# poe.net
KiCad netlist of a schematic drawn in EAGLE
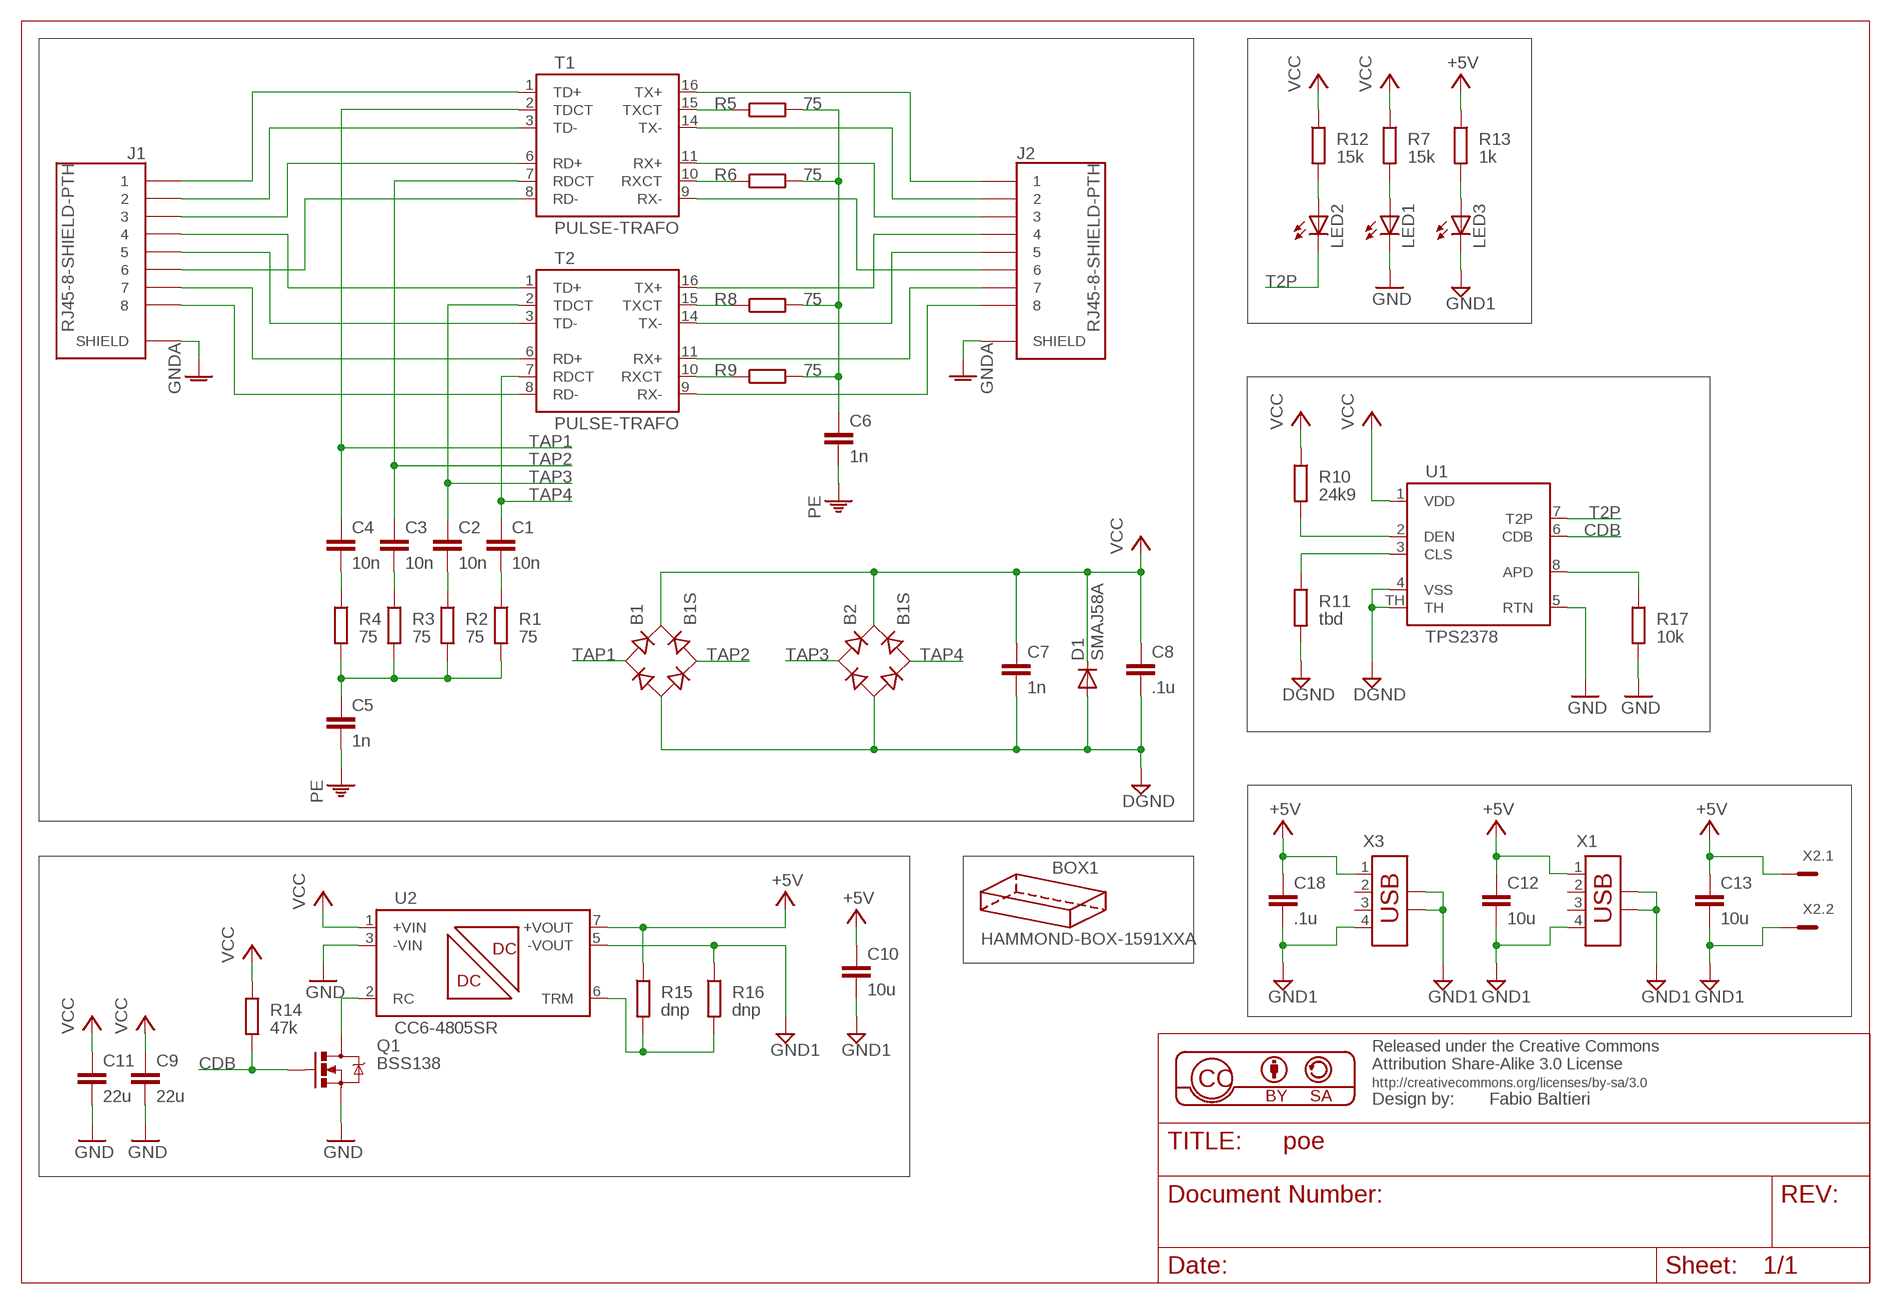
[diagram p0: schematic, sheet 1]

(export (version "E")
  (design (tool "Eeschema 10.0.6"))
  (components
    (comp (ref "B1")
      (value "B1S")
      (footprint "eagle-import:MBS")
      (libsource (lib "eagle-import") (part "BS1"))
    )
    (comp (ref "B2")
      (value "B1S")
      (footprint "eagle-import:MBS")
      (libsource (lib "eagle-import") (part "BS1"))
    )
    (comp (ref "BOX1")
      (value "HAMMOND-BOX-1591XXA")
      (footprint "eagle-import:1591XXA")
      (libsource (lib "eagle-import") (part "HAMMOND-BOX-1591XXA"))
    )
    (comp (ref "C1")
      (value "10n")
      (footprint "eagle-import:C0603")
      (libsource (lib "eagle-import") (part "C-EUC0603"))
    )
    (comp (ref "C2")
      (value "10n")
      (footprint "eagle-import:C0603")
      (libsource (lib "eagle-import") (part "C-EUC0603"))
    )
    (comp (ref "C3")
      (value "10n")
      (footprint "eagle-import:C0603")
      (libsource (lib "eagle-import") (part "C-EUC0603"))
    )
    (comp (ref "C4")
      (value "10n")
      (footprint "eagle-import:C0603")
      (libsource (lib "eagle-import") (part "C-EUC0603"))
    )
    (comp (ref "C5")
      (value "1n")
      (footprint "eagle-import:C0603")
      (libsource (lib "eagle-import") (part "C-EUC0603"))
    )
    (comp (ref "C6")
      (value "1n")
      (footprint "eagle-import:C0603")
      (libsource (lib "eagle-import") (part "C-EUC0603"))
    )
    (comp (ref "C7")
      (value "1n")
      (footprint "eagle-import:C0603")
      (libsource (lib "eagle-import") (part "C-EUC0603"))
    )
    (comp (ref "C8")
      (value ".1u")
      (footprint "eagle-import:C0603")
      (libsource (lib "eagle-import") (part "C-EUC0603"))
    )
    (comp (ref "C9")
      (value "22u")
      (footprint "eagle-import:C1206")
      (libsource (lib "eagle-import") (part "C-EUC1206"))
    )
    (comp (ref "C10")
      (value "10u")
      (footprint "eagle-import:C0805")
      (libsource (lib "eagle-import") (part "C-EUC0805"))
    )
    (comp (ref "C11")
      (value "22u")
      (footprint "eagle-import:C1206")
      (libsource (lib "eagle-import") (part "C-EUC1206"))
    )
    (comp (ref "C12")
      (value "10u")
      (footprint "eagle-import:C0603")
      (libsource (lib "eagle-import") (part "C-EUC0603"))
    )
    (comp (ref "C13")
      (value "10u")
      (footprint "eagle-import:C0603")
      (libsource (lib "eagle-import") (part "C-EUC0603"))
    )
    (comp (ref "C18")
      (value ".1u")
      (footprint "eagle-import:C0603")
      (libsource (lib "eagle-import") (part "C-EUC0603"))
    )
    (comp (ref "D1")
      (value "SMAJ58A")
      (footprint "eagle-import:SMA-DIODE")
      (libsource (lib "eagle-import") (part "DIODESMA"))
    )
    (comp (ref "J1")
      (value "RJ45-8-SHIELD-PTH")
      (footprint "eagle-import:RJ45-8-SHIELD")
      (libsource (lib "eagle-import") (part "RJ45-8-SHIELD-PTH"))
    )
    (comp (ref "J2")
      (value "RJ45-8-SHIELD-PTH")
      (footprint "eagle-import:RJ45-8-SHIELD")
      (libsource (lib "eagle-import") (part "RJ45-8-SHIELD-PTH"))
    )
    (comp (ref "LED1")
      (value "LEDSML0805")
      (footprint "eagle-import:SML0805")
      (libsource (lib "eagle-import") (part "LEDSML0805"))
    )
    (comp (ref "LED2")
      (value "LEDSML0805")
      (footprint "eagle-import:SML0805")
      (libsource (lib "eagle-import") (part "LEDSML0805"))
    )
    (comp (ref "LED3")
      (value "LEDSML0805")
      (footprint "eagle-import:SML0805")
      (libsource (lib "eagle-import") (part "LEDSML0805"))
    )
    (comp (ref "Q1")
      (value "BSS138")
      (footprint "eagle-import:SOT23-3")
      (libsource (lib "eagle-import") (part "BSS138TRANS-00830"))
    )
    (comp (ref "R1")
      (value "75")
      (footprint "eagle-import:R0603")
      (libsource (lib "eagle-import") (part "R-EU_R0603"))
    )
    (comp (ref "R2")
      (value "75")
      (footprint "eagle-import:R0603")
      (libsource (lib "eagle-import") (part "R-EU_R0603"))
    )
    (comp (ref "R3")
      (value "75")
      (footprint "eagle-import:R0603")
      (libsource (lib "eagle-import") (part "R-EU_R0603"))
    )
    (comp (ref "R4")
      (value "75")
      (footprint "eagle-import:R0603")
      (libsource (lib "eagle-import") (part "R-EU_R0603"))
    )
    (comp (ref "R5")
      (value "75")
      (footprint "eagle-import:R0603")
      (libsource (lib "eagle-import") (part "R-EU_R0603"))
    )
    (comp (ref "R6")
      (value "75")
      (footprint "eagle-import:R0603")
      (libsource (lib "eagle-import") (part "R-EU_R0603"))
    )
    (comp (ref "R7")
      (value "15k")
      (footprint "eagle-import:R0603")
      (libsource (lib "eagle-import") (part "R-EU_R0603"))
    )
    (comp (ref "R8")
      (value "75")
      (footprint "eagle-import:R0603")
      (libsource (lib "eagle-import") (part "R-EU_R0603"))
    )
    (comp (ref "R9")
      (value "75")
      (footprint "eagle-import:R0603")
      (libsource (lib "eagle-import") (part "R-EU_R0603"))
    )
    (comp (ref "R10")
      (value "24k9")
      (footprint "eagle-import:R0603")
      (libsource (lib "eagle-import") (part "R-EU_R0603"))
    )
    (comp (ref "R11")
      (value "tbd")
      (footprint "eagle-import:R0603")
      (libsource (lib "eagle-import") (part "R-EU_R0603"))
    )
    (comp (ref "R12")
      (value "15k")
      (footprint "eagle-import:R0603")
      (libsource (lib "eagle-import") (part "R-EU_R0603"))
    )
    (comp (ref "R13")
      (value "1k")
      (footprint "eagle-import:R0603")
      (libsource (lib "eagle-import") (part "R-EU_R0603"))
    )
    (comp (ref "R14")
      (value "47k")
      (footprint "eagle-import:R0603")
      (libsource (lib "eagle-import") (part "R-EU_R0603"))
    )
    (comp (ref "R15")
      (value "dnp")
      (footprint "eagle-import:R0603")
      (libsource (lib "eagle-import") (part "R-EU_R0603"))
    )
    (comp (ref "R16")
      (value "dnp")
      (footprint "eagle-import:R0603")
      (libsource (lib "eagle-import") (part "R-EU_R0603"))
    )
    (comp (ref "R17")
      (value "10k")
      (footprint "eagle-import:R0603")
      (libsource (lib "eagle-import") (part "R-EU_R0603"))
    )
    (comp (ref "T1")
      (value "PULSE-TRAFO")
      (footprint "eagle-import:PULSE-TRAFO")
      (libsource (lib "eagle-import") (part "PULSE-TRAFO"))
    )
    (comp (ref "T2")
      (value "PULSE-TRAFO")
      (footprint "eagle-import:PULSE-TRAFO")
      (libsource (lib "eagle-import") (part "PULSE-TRAFO"))
    )
    (comp (ref "U1")
      (value "TPS2378")
      (footprint "eagle-import:SOIC8-POWERPAD")
      (libsource (lib "eagle-import") (part "TPS2378"))
    )
    (comp (ref "U2")
      (value "CC6-4805SR")
      (footprint "eagle-import:CC6-XXXXSR-E")
      (libsource (lib "eagle-import") (part "CC6-4805SR"))
    )
    (comp (ref "X1")
      (value "USB-787616")
      (footprint "eagle-import:USB")
      (libsource (lib "eagle-import") (part "USB-787616"))
    )
    (comp (ref "X2")
      (value "MC2")
      (footprint "eagle-import:MC2")
      (libsource (lib "eagle-import") (part "MC2"))
    )
    (comp (ref "X3")
      (value "USB-787616")
      (footprint "eagle-import:USB")
      (libsource (lib "eagle-import") (part "USB-787616"))
    )
  )
  (nets
    (net (code "1") (name "+5V") (class "Default")
      (node (ref "C10") (pin "1") (pinfunction "1_1") (pintype "passive"))
      (node (ref "C12") (pin "1") (pinfunction "1_1") (pintype "passive"))
      (node (ref "C13") (pin "1") (pinfunction "1_1") (pintype "passive"))
      (node (ref "C18") (pin "1") (pinfunction "1_1") (pintype "passive"))
      (node (ref "R13") (pin "1") (pinfunction "1_1") (pintype "passive"))
      (node (ref "R15") (pin "1") (pinfunction "1_1") (pintype "passive"))
      (node (ref "U2") (pin "7") (pinfunction "+VOUT_7") (pintype "bidirectional"))
      (node (ref "X1") (pin "1") (pinfunction "1_1") (pintype "passive"))
      (node (ref "X2") (pin "1") (pinfunction "SK_1") (pintype "passive"))
      (node (ref "X3") (pin "1") (pinfunction "1_1") (pintype "passive"))
    )
    (net (code "2") (name "/CDB") (class "Default")
      (node (ref "Q1") (pin "1") (pinfunction "G_1") (pintype "passive"))
      (node (ref "R14") (pin "2") (pinfunction "2_2") (pintype "passive"))
      (node (ref "U1") (pin "6") (pinfunction "CDB_6") (pintype "bidirectional"))
    )
    (net (code "3") (name "/T2P") (class "Default")
      (node (ref "LED2") (pin "C") (pinfunction "C_C") (pintype "passive"))
      (node (ref "U1") (pin "7") (pinfunction "T2P_7") (pintype "bidirectional"))
    )
    (net (code "4") (name "/TAP1") (class "Default")
      (node (ref "B1") (pin "AC1") (pinfunction "AC1_AC1") (pintype "passive"))
      (node (ref "C4") (pin "1") (pinfunction "1_1") (pintype "passive"))
      (node (ref "T1") (pin "2") (pinfunction "TDCT_2") (pintype "bidirectional"))
    )
    (net (code "5") (name "/TAP2") (class "Default")
      (node (ref "B1") (pin "AC2") (pinfunction "AC2_AC2") (pintype "passive"))
      (node (ref "C3") (pin "1") (pinfunction "1_1") (pintype "passive"))
      (node (ref "T1") (pin "7") (pinfunction "RDCT_7") (pintype "bidirectional"))
    )
    (net (code "6") (name "/TAP3") (class "Default")
      (node (ref "B2") (pin "AC1") (pinfunction "AC1_AC1") (pintype "passive"))
      (node (ref "C2") (pin "1") (pinfunction "1_1") (pintype "passive"))
      (node (ref "T2") (pin "2") (pinfunction "TDCT_2") (pintype "bidirectional"))
    )
    (net (code "7") (name "/TAP4") (class "Default")
      (node (ref "B2") (pin "AC2") (pinfunction "AC2_AC2") (pintype "passive"))
      (node (ref "C1") (pin "1") (pinfunction "1_1") (pintype "passive"))
      (node (ref "T2") (pin "7") (pinfunction "RDCT_7") (pintype "bidirectional"))
    )
    (net (code "8") (name "DGND") (class "Default")
      (node (ref "B1") (pin "-") (pinfunction "-_-") (pintype "passive"))
      (node (ref "B2") (pin "-") (pinfunction "-_-") (pintype "passive"))
      (node (ref "C7") (pin "2") (pinfunction "2_2") (pintype "passive"))
      (node (ref "C8") (pin "2") (pinfunction "2_2") (pintype "passive"))
      (node (ref "D1") (pin "A") (pinfunction "A_A") (pintype "passive"))
      (node (ref "R11") (pin "2") (pinfunction "2_2") (pintype "passive"))
      (node (ref "U1") (pin "4") (pinfunction "VSS_4") (pintype "bidirectional"))
      (node (ref "U1") (pin "TH") (pinfunction "TH_TH") (pintype "bidirectional"))
    )
    (net (code "9") (name "GND") (class "Default")
      (node (ref "C11") (pin "2") (pinfunction "2_2") (pintype "passive"))
      (node (ref "C9") (pin "2") (pinfunction "2_2") (pintype "passive"))
      (node (ref "LED1") (pin "C") (pinfunction "C_C") (pintype "passive"))
      (node (ref "Q1") (pin "2") (pinfunction "S_2") (pintype "passive"))
      (node (ref "R17") (pin "2") (pinfunction "2_2") (pintype "passive"))
      (node (ref "U1") (pin "5") (pinfunction "RTN_5") (pintype "bidirectional"))
      (node (ref "U2") (pin "3") (pinfunction "-VIN_3") (pintype "bidirectional"))
    )
    (net (code "10") (name "GND1") (class "Default")
      (node (ref "C10") (pin "2") (pinfunction "2_2") (pintype "passive"))
      (node (ref "C12") (pin "2") (pinfunction "2_2") (pintype "passive"))
      (node (ref "C13") (pin "2") (pinfunction "2_2") (pintype "passive"))
      (node (ref "C18") (pin "2") (pinfunction "2_2") (pintype "passive"))
      (node (ref "LED3") (pin "C") (pinfunction "C_C") (pintype "passive"))
      (node (ref "R16") (pin "1") (pinfunction "1_1") (pintype "passive"))
      (node (ref "U2") (pin "5") (pinfunction "-VOUT_5") (pintype "bidirectional"))
      (node (ref "X1") (pin "4") (pinfunction "4_4") (pintype "passive"))
      (node (ref "X1") (pin "SHLD1") (pinfunction "SHLD1_SHLD1") (pintype "passive"))
      (node (ref "X1") (pin "SHLD2") (pinfunction "SHLD2_SHLD2") (pintype "passive"))
      (node (ref "X2") (pin "2") (pinfunction "SK_2") (pintype "passive"))
      (node (ref "X3") (pin "4") (pinfunction "4_4") (pintype "passive"))
      (node (ref "X3") (pin "SHLD1") (pinfunction "SHLD1_SHLD1") (pintype "passive"))
      (node (ref "X3") (pin "SHLD2") (pinfunction "SHLD2_SHLD2") (pintype "passive"))
    )
    (net (code "11") (name "GNDA") (class "Default")
      (node (ref "J1") (pin "P$1") (pinfunction "SHIELD_P$1") (pintype "bidirectional"))
      (node (ref "J1") (pin "P$2") (pinfunction "SHIELD_P$2") (pintype "bidirectional"))
      (node (ref "J2") (pin "P$1") (pinfunction "SHIELD_P$1") (pintype "bidirectional"))
      (node (ref "J2") (pin "P$2") (pinfunction "SHIELD_P$2") (pintype "bidirectional"))
    )
    (net (code "12") (name "Net-(C1-Pad2)") (class "Default")
      (node (ref "C1") (pin "2") (pinfunction "2_2") (pintype "passive"))
      (node (ref "R1") (pin "1") (pinfunction "1_1") (pintype "passive"))
    )
    (net (code "13") (name "Net-(C2-Pad2)") (class "Default")
      (node (ref "C2") (pin "2") (pinfunction "2_2") (pintype "passive"))
      (node (ref "R2") (pin "1") (pinfunction "1_1") (pintype "passive"))
    )
    (net (code "14") (name "Net-(C3-Pad2)") (class "Default")
      (node (ref "C3") (pin "2") (pinfunction "2_2") (pintype "passive"))
      (node (ref "R3") (pin "1") (pinfunction "1_1") (pintype "passive"))
    )
    (net (code "15") (name "Net-(C4-Pad2)") (class "Default")
      (node (ref "C4") (pin "2") (pinfunction "2_2") (pintype "passive"))
      (node (ref "R4") (pin "1") (pinfunction "1_1") (pintype "passive"))
    )
    (net (code "16") (name "Net-(C5-Pad1)") (class "Default")
      (node (ref "C5") (pin "1") (pinfunction "1_1") (pintype "passive"))
      (node (ref "R1") (pin "2") (pinfunction "2_2") (pintype "passive"))
      (node (ref "R2") (pin "2") (pinfunction "2_2") (pintype "passive"))
      (node (ref "R3") (pin "2") (pinfunction "2_2") (pintype "passive"))
      (node (ref "R4") (pin "2") (pinfunction "2_2") (pintype "passive"))
    )
    (net (code "17") (name "Net-(C6-Pad1)") (class "Default")
      (node (ref "C6") (pin "1") (pinfunction "1_1") (pintype "passive"))
      (node (ref "R5") (pin "2") (pinfunction "2_2") (pintype "passive"))
      (node (ref "R6") (pin "2") (pinfunction "2_2") (pintype "passive"))
      (node (ref "R8") (pin "2") (pinfunction "2_2") (pintype "passive"))
      (node (ref "R9") (pin "2") (pinfunction "2_2") (pintype "passive"))
    )
    (net (code "18") (name "Net-(LED1-PadA)") (class "Default")
      (node (ref "LED1") (pin "A") (pinfunction "A_A") (pintype "passive"))
      (node (ref "R7") (pin "2") (pinfunction "2_2") (pintype "passive"))
    )
    (net (code "19") (name "Net-(LED2-PadA)") (class "Default")
      (node (ref "LED2") (pin "A") (pinfunction "A_A") (pintype "passive"))
      (node (ref "R12") (pin "2") (pinfunction "2_2") (pintype "passive"))
    )
    (net (code "20") (name "Net-(LED3-PadA)") (class "Default")
      (node (ref "LED3") (pin "A") (pinfunction "A_A") (pintype "passive"))
      (node (ref "R13") (pin "2") (pinfunction "2_2") (pintype "passive"))
    )
    (net (code "21") (name "Net-(Q1-D)") (class "Default")
      (node (ref "Q1") (pin "3") (pinfunction "D_3") (pintype "passive"))
      (node (ref "U2") (pin "2") (pinfunction "RC_2") (pintype "bidirectional"))
    )
    (net (code "22") (name "Net-(T1-RD+)") (class "Default")
      (node (ref "J1") (pin "3") (pinfunction "3_3") (pintype "bidirectional"))
      (node (ref "T1") (pin "6") (pinfunction "RD+_6") (pintype "bidirectional"))
    )
    (net (code "23") (name "Net-(T1-RD-)") (class "Default")
      (node (ref "J1") (pin "6") (pinfunction "6_6") (pintype "bidirectional"))
      (node (ref "T1") (pin "8") (pinfunction "RD-_8") (pintype "bidirectional"))
    )
    (net (code "24") (name "Net-(T1-RX+)") (class "Default")
      (node (ref "J2") (pin "3") (pinfunction "3_3") (pintype "bidirectional"))
      (node (ref "T1") (pin "11") (pinfunction "RX+_11") (pintype "bidirectional"))
    )
    (net (code "25") (name "Net-(T1-RX-)") (class "Default")
      (node (ref "J2") (pin "6") (pinfunction "6_6") (pintype "bidirectional"))
      (node (ref "T1") (pin "9") (pinfunction "RX-_9") (pintype "bidirectional"))
    )
    (net (code "26") (name "Net-(T1-RXCT)") (class "Default")
      (node (ref "R6") (pin "1") (pinfunction "1_1") (pintype "passive"))
      (node (ref "T1") (pin "10") (pinfunction "RXCT_10") (pintype "bidirectional"))
    )
    (net (code "27") (name "Net-(T1-TD+)") (class "Default")
      (node (ref "J1") (pin "1") (pinfunction "1_1") (pintype "bidirectional"))
      (node (ref "T1") (pin "1") (pinfunction "TD+_1") (pintype "bidirectional"))
    )
    (net (code "28") (name "Net-(T1-TD-)") (class "Default")
      (node (ref "J1") (pin "2") (pinfunction "2_2") (pintype "bidirectional"))
      (node (ref "T1") (pin "3") (pinfunction "TD-_3") (pintype "bidirectional"))
    )
    (net (code "29") (name "Net-(T1-TX+)") (class "Default")
      (node (ref "J2") (pin "1") (pinfunction "1_1") (pintype "bidirectional"))
      (node (ref "T1") (pin "16") (pinfunction "TX+_16") (pintype "bidirectional"))
    )
    (net (code "30") (name "Net-(T1-TX-)") (class "Default")
      (node (ref "J2") (pin "2") (pinfunction "2_2") (pintype "bidirectional"))
      (node (ref "T1") (pin "14") (pinfunction "TX-_14") (pintype "bidirectional"))
    )
    (net (code "31") (name "Net-(T1-TXCT)") (class "Default")
      (node (ref "R5") (pin "1") (pinfunction "1_1") (pintype "passive"))
      (node (ref "T1") (pin "15") (pinfunction "TXCT_15") (pintype "bidirectional"))
    )
    (net (code "32") (name "Net-(T2-RD+)") (class "Default")
      (node (ref "J1") (pin "7") (pinfunction "7_7") (pintype "bidirectional"))
      (node (ref "T2") (pin "6") (pinfunction "RD+_6") (pintype "bidirectional"))
    )
    (net (code "33") (name "Net-(T2-RD-)") (class "Default")
      (node (ref "J1") (pin "8") (pinfunction "8_8") (pintype "bidirectional"))
      (node (ref "T2") (pin "8") (pinfunction "RD-_8") (pintype "bidirectional"))
    )
    (net (code "34") (name "Net-(T2-RX+)") (class "Default")
      (node (ref "J2") (pin "7") (pinfunction "7_7") (pintype "bidirectional"))
      (node (ref "T2") (pin "11") (pinfunction "RX+_11") (pintype "bidirectional"))
    )
    (net (code "35") (name "Net-(T2-RX-)") (class "Default")
      (node (ref "J2") (pin "8") (pinfunction "8_8") (pintype "bidirectional"))
      (node (ref "T2") (pin "9") (pinfunction "RX-_9") (pintype "bidirectional"))
    )
    (net (code "36") (name "Net-(T2-RXCT)") (class "Default")
      (node (ref "R9") (pin "1") (pinfunction "1_1") (pintype "passive"))
      (node (ref "T2") (pin "10") (pinfunction "RXCT_10") (pintype "bidirectional"))
    )
    (net (code "37") (name "Net-(T2-TD+)") (class "Default")
      (node (ref "J1") (pin "4") (pinfunction "4_4") (pintype "bidirectional"))
      (node (ref "T2") (pin "1") (pinfunction "TD+_1") (pintype "bidirectional"))
    )
    (net (code "38") (name "Net-(T2-TD-)") (class "Default")
      (node (ref "J1") (pin "5") (pinfunction "5_5") (pintype "bidirectional"))
      (node (ref "T2") (pin "3") (pinfunction "TD-_3") (pintype "bidirectional"))
    )
    (net (code "39") (name "Net-(T2-TX+)") (class "Default")
      (node (ref "J2") (pin "4") (pinfunction "4_4") (pintype "bidirectional"))
      (node (ref "T2") (pin "16") (pinfunction "TX+_16") (pintype "bidirectional"))
    )
    (net (code "40") (name "Net-(T2-TX-)") (class "Default")
      (node (ref "J2") (pin "5") (pinfunction "5_5") (pintype "bidirectional"))
      (node (ref "T2") (pin "14") (pinfunction "TX-_14") (pintype "bidirectional"))
    )
    (net (code "41") (name "Net-(T2-TXCT)") (class "Default")
      (node (ref "R8") (pin "1") (pinfunction "1_1") (pintype "passive"))
      (node (ref "T2") (pin "15") (pinfunction "TXCT_15") (pintype "bidirectional"))
    )
    (net (code "42") (name "Net-(U1-APD)") (class "Default")
      (node (ref "R17") (pin "1") (pinfunction "1_1") (pintype "passive"))
      (node (ref "U1") (pin "8") (pinfunction "APD_8") (pintype "bidirectional"))
    )
    (net (code "43") (name "Net-(U1-CLS)") (class "Default")
      (node (ref "R11") (pin "1") (pinfunction "1_1") (pintype "passive"))
      (node (ref "U1") (pin "3") (pinfunction "CLS_3") (pintype "bidirectional"))
    )
    (net (code "44") (name "Net-(U1-DEN)") (class "Default")
      (node (ref "R10") (pin "2") (pinfunction "2_2") (pintype "passive"))
      (node (ref "U1") (pin "2") (pinfunction "DEN_2") (pintype "bidirectional"))
    )
    (net (code "45") (name "Net-(U2-TRM)") (class "Default")
      (node (ref "R15") (pin "2") (pinfunction "2_2") (pintype "passive"))
      (node (ref "R16") (pin "2") (pinfunction "2_2") (pintype "passive"))
      (node (ref "U2") (pin "6") (pinfunction "TRM_6") (pintype "bidirectional"))
    )
    (net (code "46") (name "PE") (class "Default")
      (node (ref "C5") (pin "2") (pinfunction "2_2") (pintype "passive"))
      (node (ref "C6") (pin "2") (pinfunction "2_2") (pintype "passive"))
    )
    (net (code "47") (name "VCC") (class "Default")
      (node (ref "B1") (pin "+") (pinfunction "+_+") (pintype "passive"))
      (node (ref "B2") (pin "+") (pinfunction "+_+") (pintype "passive"))
      (node (ref "C11") (pin "1") (pinfunction "1_1") (pintype "passive"))
      (node (ref "C7") (pin "1") (pinfunction "1_1") (pintype "passive"))
      (node (ref "C8") (pin "1") (pinfunction "1_1") (pintype "passive"))
      (node (ref "C9") (pin "1") (pinfunction "1_1") (pintype "passive"))
      (node (ref "D1") (pin "C") (pinfunction "C_C") (pintype "passive"))
      (node (ref "R10") (pin "1") (pinfunction "1_1") (pintype "passive"))
      (node (ref "R12") (pin "1") (pinfunction "1_1") (pintype "passive"))
      (node (ref "R14") (pin "1") (pinfunction "1_1") (pintype "passive"))
      (node (ref "R7") (pin "1") (pinfunction "1_1") (pintype "passive"))
      (node (ref "U1") (pin "1") (pinfunction "VDD_1") (pintype "bidirectional"))
      (node (ref "U2") (pin "1") (pinfunction "+VIN_1") (pintype "bidirectional"))
    )
    (net (code "48") (name "unconnected-(X1-Pad2)") (class "Default")
      (node (ref "X1") (pin "2") (pinfunction "2_2") (pintype "passive"))
    )
    (net (code "49") (name "unconnected-(X1-Pad3)") (class "Default")
      (node (ref "X1") (pin "3") (pinfunction "3_3") (pintype "passive"))
    )
    (net (code "50") (name "unconnected-(X3-Pad2)") (class "Default")
      (node (ref "X3") (pin "2") (pinfunction "2_2") (pintype "passive"))
    )
    (net (code "51") (name "unconnected-(X3-Pad3)") (class "Default")
      (node (ref "X3") (pin "3") (pinfunction "3_3") (pintype "passive"))
    )
  )
)
